# FMS.net
KiCad netlist of a schematic drawn in EAGLE
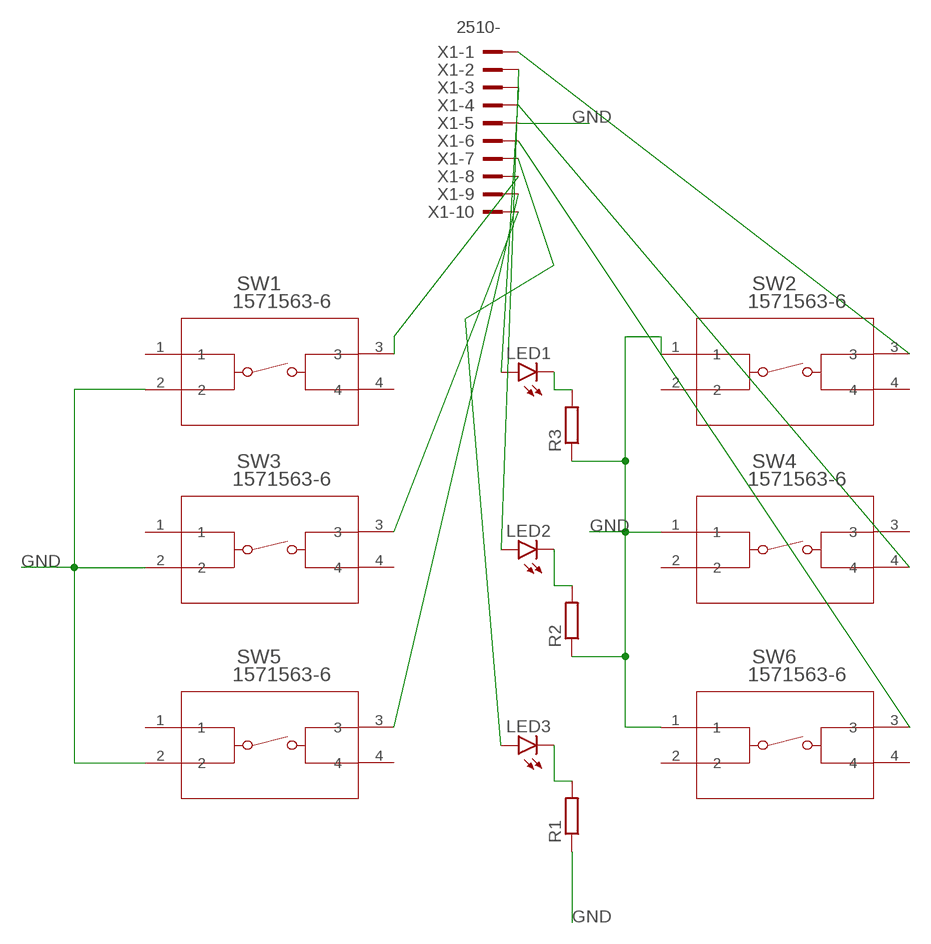
[diagram p0: schematic, sheet 1]

(export (version "E")
  (design (tool "Eeschema 10.0.6"))
  (components
    (comp (ref "LED1")
      (value "LEDCHIPLED_1206")
      (footprint "eagle-import:CHIPLED_1206")
      (libsource (lib "eagle-import") (part "LEDCHIPLED_1206"))
    )
    (comp (ref "LED2")
      (value "LEDCHIPLED_1206")
      (footprint "eagle-import:CHIPLED_1206")
      (libsource (lib "eagle-import") (part "LEDCHIPLED_1206"))
    )
    (comp (ref "LED3")
      (value "LEDCHIPLED_1206")
      (footprint "eagle-import:CHIPLED_1206")
      (libsource (lib "eagle-import") (part "LEDCHIPLED_1206"))
    )
    (comp (ref "R1")
      (value "R-EU_R1206")
      (footprint "eagle-import:R1206")
      (libsource (lib "eagle-import") (part "R-EU_R1206"))
    )
    (comp (ref "R2")
      (value "R-EU_R1206")
      (footprint "eagle-import:R1206")
      (libsource (lib "eagle-import") (part "R-EU_R1206"))
    )
    (comp (ref "R3")
      (value "R-EU_R1206")
      (footprint "eagle-import:R1206")
      (libsource (lib "eagle-import") (part "R-EU_R1206"))
    )
    (comp (ref "SW1")
      (value "1571563-6")
      (footprint "eagle-import:SW4_1437565-E")
      (fields (field (name "COPYRIGHT") "Copyright (C) 2016 Accelerated Designs. All rights reserved"))
      (libsource (lib "eagle-import") (part "1571563-6"))
    )
    (comp (ref "SW2")
      (value "1571563-6")
      (footprint "eagle-import:SW4_1437565-E")
      (fields (field (name "COPYRIGHT") "Copyright (C) 2016 Accelerated Designs. All rights reserved"))
      (libsource (lib "eagle-import") (part "1571563-6"))
    )
    (comp (ref "SW3")
      (value "1571563-6")
      (footprint "eagle-import:SW4_1437565-E")
      (fields (field (name "COPYRIGHT") "Copyright (C) 2016 Accelerated Designs. All rights reserved"))
      (libsource (lib "eagle-import") (part "1571563-6"))
    )
    (comp (ref "SW4")
      (value "1571563-6")
      (footprint "eagle-import:SW4_1437565-E")
      (fields (field (name "COPYRIGHT") "Copyright (C) 2016 Accelerated Designs. All rights reserved"))
      (libsource (lib "eagle-import") (part "1571563-6"))
    )
    (comp (ref "SW5")
      (value "1571563-6")
      (footprint "eagle-import:SW4_1437565-E")
      (fields (field (name "COPYRIGHT") "Copyright (C) 2016 Accelerated Designs. All rights reserved"))
      (libsource (lib "eagle-import") (part "1571563-6"))
    )
    (comp (ref "SW6")
      (value "1571563-6")
      (footprint "eagle-import:SW4_1437565-E")
      (fields (field (name "COPYRIGHT") "Copyright (C) 2016 Accelerated Designs. All rights reserved"))
      (libsource (lib "eagle-import") (part "1571563-6"))
    )
    (comp (ref "X1")
      (value "2510-")
      (footprint "eagle-import:PAK100_2500-10")
      (fields (field (name "MF") "3M") (field (name "MPN") "2510-6002UB"))
      (libsource (lib "eagle-import") (part "2510-"))
    )
  )
  (nets
    (net (code "1") (name "/GND") (class "Default")
      (node (ref "R1") (pin "1") (pinfunction "1_1") (pintype "passive"))
      (node (ref "R2") (pin "1") (pinfunction "1_1") (pintype "passive"))
      (node (ref "R3") (pin "1") (pinfunction "1_1") (pintype "passive"))
      (node (ref "SW1") (pin "2") (pinfunction "2_2") (pintype "passive"))
      (node (ref "SW2") (pin "1") (pinfunction "1_1") (pintype "passive"))
      (node (ref "SW3") (pin "2") (pinfunction "2_2") (pintype "passive"))
      (node (ref "SW4") (pin "1") (pinfunction "1_1") (pintype "passive"))
      (node (ref "SW5") (pin "2") (pinfunction "2_2") (pintype "passive"))
      (node (ref "SW6") (pin "1") (pinfunction "1_1") (pintype "passive"))
      (node (ref "X1") (pin "5") (pinfunction "KL_5") (pintype "passive"))
    )
    (net (code "2") (name "Net-(LED1-PadC)") (class "Default")
      (node (ref "LED1") (pin "C") (pinfunction "C_C") (pintype "passive"))
      (node (ref "R3") (pin "2") (pinfunction "2_2") (pintype "passive"))
    )
    (net (code "3") (name "Net-(LED2-PadC)") (class "Default")
      (node (ref "LED2") (pin "C") (pinfunction "C_C") (pintype "passive"))
      (node (ref "R2") (pin "2") (pinfunction "2_2") (pintype "passive"))
    )
    (net (code "4") (name "Net-(LED3-PadC)") (class "Default")
      (node (ref "LED3") (pin "C") (pinfunction "C_C") (pintype "passive"))
      (node (ref "R1") (pin "2") (pinfunction "2_2") (pintype "passive"))
    )
    (net (code "5") (name "Net-(X1A-KL)") (class "Default")
      (node (ref "SW2") (pin "3") (pinfunction "3_3") (pintype "passive"))
      (node (ref "X1") (pin "1") (pinfunction "KL_1") (pintype "passive"))
    )
    (net (code "6") (name "Net-(X1B-KL)") (class "Default")
      (node (ref "SW3") (pin "3") (pinfunction "3_3") (pintype "passive"))
      (node (ref "X1") (pin "10") (pinfunction "KL_10") (pintype "passive"))
    )
    (net (code "7") (name "Net-(X1C-KL)") (class "Default")
      (node (ref "LED2") (pin "A") (pinfunction "A_A") (pintype "passive"))
      (node (ref "X1") (pin "2") (pinfunction "KL_2") (pintype "passive"))
    )
    (net (code "8") (name "Net-(X1D-KL)") (class "Default")
      (node (ref "LED1") (pin "A") (pinfunction "A_A") (pintype "passive"))
      (node (ref "X1") (pin "3") (pinfunction "KL_3") (pintype "passive"))
    )
    (net (code "9") (name "Net-(X1E-KL)") (class "Default")
      (node (ref "SW4") (pin "4") (pinfunction "4_4") (pintype "passive"))
      (node (ref "X1") (pin "4") (pinfunction "KL_4") (pintype "passive"))
    )
    (net (code "10") (name "Net-(X1G-KL)") (class "Default")
      (node (ref "SW6") (pin "3") (pinfunction "3_3") (pintype "passive"))
      (node (ref "X1") (pin "6") (pinfunction "KL_6") (pintype "passive"))
    )
    (net (code "11") (name "Net-(X1H-KL)") (class "Default")
      (node (ref "LED3") (pin "A") (pinfunction "A_A") (pintype "passive"))
      (node (ref "X1") (pin "7") (pinfunction "KL_7") (pintype "passive"))
    )
    (net (code "12") (name "Net-(X1I-KL)") (class "Default")
      (node (ref "SW1") (pin "3") (pinfunction "3_3") (pintype "passive"))
      (node (ref "X1") (pin "8") (pinfunction "KL_8") (pintype "passive"))
    )
    (net (code "13") (name "Net-(X1J-KL)") (class "Default")
      (node (ref "SW5") (pin "3") (pinfunction "3_3") (pintype "passive"))
      (node (ref "X1") (pin "9") (pinfunction "KL_9") (pintype "passive"))
    )
    (net (code "14") (name "unconnected-(SW1-Pad1)") (class "Default")
      (node (ref "SW1") (pin "1") (pinfunction "1_1") (pintype "passive"))
    )
    (net (code "15") (name "unconnected-(SW1-Pad4)") (class "Default")
      (node (ref "SW1") (pin "4") (pinfunction "4_4") (pintype "passive"))
    )
    (net (code "16") (name "unconnected-(SW2-Pad2)") (class "Default")
      (node (ref "SW2") (pin "2") (pinfunction "2_2") (pintype "passive"))
    )
    (net (code "17") (name "unconnected-(SW2-Pad4)") (class "Default")
      (node (ref "SW2") (pin "4") (pinfunction "4_4") (pintype "passive"))
    )
    (net (code "18") (name "unconnected-(SW3-Pad1)") (class "Default")
      (node (ref "SW3") (pin "1") (pinfunction "1_1") (pintype "passive"))
    )
    (net (code "19") (name "unconnected-(SW3-Pad4)") (class "Default")
      (node (ref "SW3") (pin "4") (pinfunction "4_4") (pintype "passive"))
    )
    (net (code "20") (name "unconnected-(SW4-Pad2)") (class "Default")
      (node (ref "SW4") (pin "2") (pinfunction "2_2") (pintype "passive"))
    )
    (net (code "21") (name "unconnected-(SW4-Pad3)") (class "Default")
      (node (ref "SW4") (pin "3") (pinfunction "3_3") (pintype "passive"))
    )
    (net (code "22") (name "unconnected-(SW5-Pad1)") (class "Default")
      (node (ref "SW5") (pin "1") (pinfunction "1_1") (pintype "passive"))
    )
    (net (code "23") (name "unconnected-(SW5-Pad4)") (class "Default")
      (node (ref "SW5") (pin "4") (pinfunction "4_4") (pintype "passive"))
    )
    (net (code "24") (name "unconnected-(SW6-Pad2)") (class "Default")
      (node (ref "SW6") (pin "2") (pinfunction "2_2") (pintype "passive"))
    )
    (net (code "25") (name "unconnected-(SW6-Pad4)") (class "Default")
      (node (ref "SW6") (pin "4") (pinfunction "4_4") (pintype "passive"))
    )
  )
)
